# EQ_A.net
KiCad netlist of a schematic drawn in Altium Designer
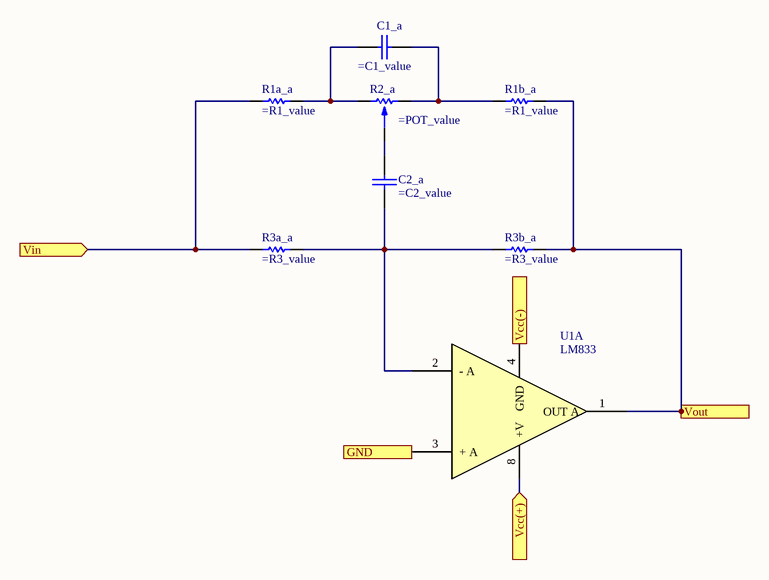
[diagram p0: EQ_A.SchDoc]

(export (version "E")
  (design (tool "Eeschema 10.0.6"))
  (components
    (comp (ref "C1_a") (value "~") (footprint "CAP200") (libsource (lib "LIBEBAL") (part "CAP")))
    (comp (ref "C2_a") (value "~") (footprint "CAP200") (libsource (lib "LIBEBAL") (part "CAP")))
    (comp (ref "R1a_a") (value "~") (footprint "0805") (libsource (lib "LIBEBAL") (part "RES")))
    (comp (ref "R1b_a") (value "~") (footprint "0805") (libsource (lib "LIBEBAL") (part "RES")))
    (comp (ref "R2_a")
      (value "~")
      (footprint "POTENCIOMETRO")
      (libsource (lib "LIBEBAL") (part "POTENCIOMETRO"))
    )
    (comp (ref "R3a_a") (value "~") (footprint "0805") (libsource (lib "LIBEBAL") (part "RES")))
    (comp (ref "R3b_a") (value "~") (footprint "0805") (libsource (lib "LIBEBAL") (part "RES")))
    (comp (ref "U1")
      (value "LM833")
      (footprint "DIP8")
      (description "Dual Audio Operational Amplifier")
      (libsource (lib "LIBEBAL") (part "LM833"))
    )
  )
  (nets
    (net (code "1") (name "/GND") (class "Default")
      (node (ref "U1") (pin "3") (pinfunction "+_A_3") (pintype "passive"))
    )
    (net (code "2") (name "/Vcc(+)") (class "Default")
      (node (ref "U1") (pin "8") (pinfunction "+V_8") (pintype "passive"))
    )
    (net (code "4") (name "/Vcc(-)") (class "Default")
      (node (ref "U1") (pin "4") (pinfunction "GND_4") (pintype "passive"))
    )
    (net (code "5") (name "/Vin") (class "Default")
      (node (ref "R1a_a") (pin "1") (pinfunction "1_1") (pintype "passive"))
      (node (ref "R3a_a") (pin "1") (pinfunction "1_1") (pintype "passive"))
    )
    (net (code "6") (name "/Vout") (class "Default")
      (node (ref "R1b_a") (pin "2") (pinfunction "2_2") (pintype "passive"))
      (node (ref "R3b_a") (pin "2") (pinfunction "2_2") (pintype "passive"))
      (node (ref "U1") (pin "1") (pinfunction "OUT_A_1") (pintype "passive"))
    )
    (net (code "7") (name "Net-(C1_a-Pad1)") (class "Default")
      (node (ref "C1_a") (pin "1") (pinfunction "1_1") (pintype "passive"))
      (node (ref "R1a_a") (pin "2") (pinfunction "2_2") (pintype "passive"))
      (node (ref "R2_a") (pin "3") (pinfunction "3_3") (pintype "passive"))
    )
    (net (code "8") (name "Net-(C1_a-Pad2)") (class "Default")
      (node (ref "C1_a") (pin "2") (pinfunction "2_2") (pintype "passive"))
      (node (ref "R1b_a") (pin "1") (pinfunction "1_1") (pintype "passive"))
      (node (ref "R2_a") (pin "1") (pinfunction "1_1") (pintype "passive"))
    )
    (net (code "9") (name "Net-(C2_a-Pad1)") (class "Default")
      (node (ref "C2_a") (pin "1") (pinfunction "1_1") (pintype "passive"))
      (node (ref "R2_a") (pin "2") (pinfunction "2_2") (pintype "passive"))
    )
    (net (code "10") (name "Net-(U1A--_A)") (class "Default")
      (node (ref "C2_a") (pin "2") (pinfunction "2_2") (pintype "passive"))
      (node (ref "R3a_a") (pin "2") (pinfunction "2_2") (pintype "passive"))
      (node (ref "R3b_a") (pin "1") (pinfunction "1_1") (pintype "passive"))
      (node (ref "U1") (pin "2") (pinfunction "-_A_2") (pintype "passive"))
    )
  )
)
